# Qwiic_Quad_Relay.net
KiCad netlist of a schematic drawn in EAGLE
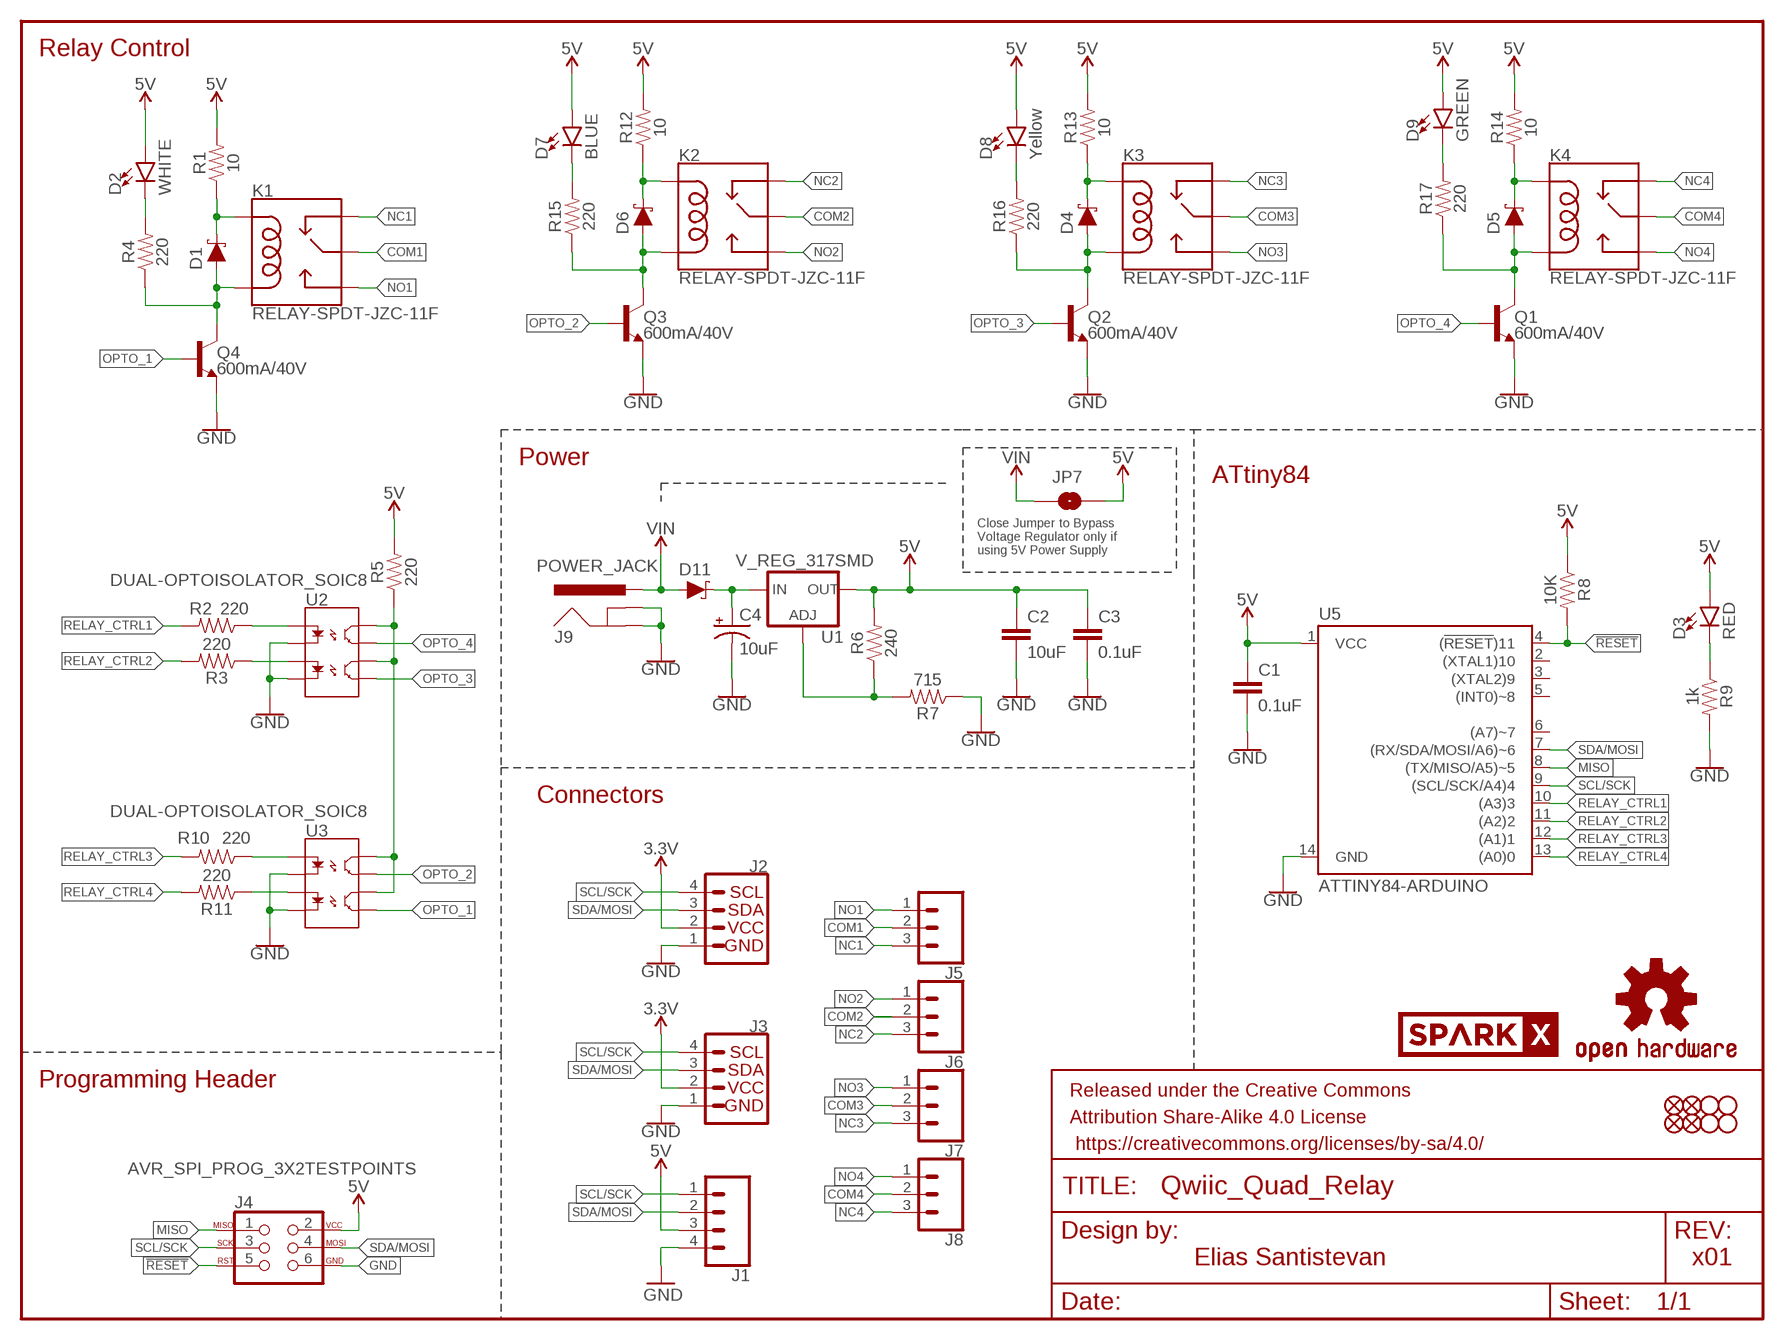
[diagram p0: schematic, sheet 1]

(export (version "E")
  (design (tool "Eeschema 10.0.6"))
  (components
    (comp (ref "C1")
      (value "0.1uF")
      (footprint "eagle-import:0603")
      (libsource (lib "eagle-import") (part "0.1UF-0603-25V-(+80/-20%)"))
    )
    (comp (ref "C2")
      (value "10uF")
      (footprint "eagle-import:0603")
      (libsource (lib "eagle-import") (part "10UF-0603-6.3V-20%"))
    )
    (comp (ref "C3")
      (value "0.1uF")
      (footprint "eagle-import:0603")
      (libsource (lib "eagle-import") (part "0.1UF-0603-25V-(+80/-20%)"))
    )
    (comp (ref "C4")
      (value "10uF")
      (footprint "eagle-import:EIA3528")
      (libsource (lib "eagle-import") (part "10UF-POLAR-EIA3528-20V-10%(TANT)"))
    )
    (comp (ref "D1")
      (value "1A/23V/620mV")
      (footprint "eagle-import:SOD-323")
      (libsource (lib "eagle-import") (part "DIODE-SCHOTTKY-BAT20J"))
    )
    (comp (ref "D2")
      (value "WHITE")
      (footprint "eagle-import:LED-0603")
      (libsource (lib "eagle-import") (part "LED-WHITE0603"))
    )
    (comp (ref "D3")
      (value "RED")
      (footprint "eagle-import:LED-0603")
      (libsource (lib "eagle-import") (part "LED-RED0603"))
    )
    (comp (ref "D4")
      (value "1A/23V/620mV")
      (footprint "eagle-import:SOD-323")
      (libsource (lib "eagle-import") (part "DIODE-SCHOTTKY-BAT20J"))
    )
    (comp (ref "D5")
      (value "1A/23V/620mV")
      (footprint "eagle-import:SOD-323")
      (libsource (lib "eagle-import") (part "DIODE-SCHOTTKY-BAT20J"))
    )
    (comp (ref "D6")
      (value "1A/23V/620mV")
      (footprint "eagle-import:SOD-323")
      (libsource (lib "eagle-import") (part "DIODE-SCHOTTKY-BAT20J"))
    )
    (comp (ref "D7")
      (value "BLUE")
      (footprint "eagle-import:LED-0603")
      (libsource (lib "eagle-import") (part "LED-BLUE0603"))
    )
    (comp (ref "D8")
      (value "Yellow")
      (footprint "eagle-import:LED-0603")
      (libsource (lib "eagle-import") (part "LED-YELLOW0603"))
    )
    (comp (ref "D9")
      (value "GREEN")
      (footprint "eagle-import:LED-0603")
      (libsource (lib "eagle-import") (part "LED-GREEN0603"))
    )
    (comp (ref "D11")
      (value "1A/40V/500mV")
      (footprint "eagle-import:SMA-DIODE")
      (libsource (lib "eagle-import") (part "DIODE-SCHOTTKY-SS14"))
    )
    (comp (ref "FRAME1")
      (value "FRAME-LETTER")
      (footprint "eagle-import:CREATIVE_COMMONS")
      (libsource (lib "eagle-import") (part "FRAME-LETTER"))
    )
    (comp (ref "J1")
      (value "CONN_041X04_NO_SILK")
      (footprint "eagle-import:1X04_NO_SILK")
      (libsource (lib "eagle-import") (part "CONN_041X04_NO_SILK"))
    )
    (comp (ref "J2")
      (value "Qwiic Right Angle")
      (footprint "eagle-import:1X04_1MM_RA")
      (libsource (lib "eagle-import") (part "I2C_STANDARDQWIIC"))
    )
    (comp (ref "J3")
      (value "Qwiic Right Angle")
      (footprint "eagle-import:1X04_1MM_RA")
      (libsource (lib "eagle-import") (part "I2C_STANDARDQWIIC"))
    )
    (comp (ref "J4")
      (value "AVR_SPI_PROG_3X2TESTPOINTS")
      (footprint "eagle-import:2X3_TEST_POINTS")
      (libsource (lib "eagle-import") (part "AVR_SPI_PROG_3X2TESTPOINTS"))
    )
    (comp (ref "J5")
      (value "CONN_03-SCREW-5MM")
      (footprint "eagle-import:SCREWTERMINAL-5MM-3")
      (libsource (lib "eagle-import") (part "CONN_03-SCREW-5MM"))
    )
    (comp (ref "J6")
      (value "CONN_03-SCREW-5MM")
      (footprint "eagle-import:SCREWTERMINAL-5MM-3")
      (libsource (lib "eagle-import") (part "CONN_03-SCREW-5MM"))
    )
    (comp (ref "J7")
      (value "CONN_03-SCREW-5MM")
      (footprint "eagle-import:SCREWTERMINAL-5MM-3")
      (libsource (lib "eagle-import") (part "CONN_03-SCREW-5MM"))
    )
    (comp (ref "J8")
      (value "CONN_03-SCREW-5MM")
      (footprint "eagle-import:SCREWTERMINAL-5MM-3")
      (libsource (lib "eagle-import") (part "CONN_03-SCREW-5MM"))
    )
    (comp (ref "J9")
      (value "POWER_JACK")
      (footprint "eagle-import:POWER_JACK_PTH")
      (libsource (lib "eagle-import") (part "POWER_JACK"))
    )
    (comp (ref "JP1")
      (value "STAND-OFF")
      (footprint "eagle-import:STAND-OFF")
      (libsource (lib "eagle-import") (part "STAND-OFF"))
    )
    (comp (ref "JP2")
      (value "FIDUCIAL1X2")
      (footprint "eagle-import:FIDUCIAL-1X2")
      (libsource (lib "eagle-import") (part "FIDUCIAL1X2"))
    )
    (comp (ref "JP3")
      (value "STAND-OFF")
      (footprint "eagle-import:STAND-OFF")
      (libsource (lib "eagle-import") (part "STAND-OFF"))
    )
    (comp (ref "JP4")
      (value "STAND-OFF")
      (footprint "eagle-import:STAND-OFF")
      (libsource (lib "eagle-import") (part "STAND-OFF"))
    )
    (comp (ref "JP5")
      (value "STAND-OFF")
      (footprint "eagle-import:STAND-OFF")
      (libsource (lib "eagle-import") (part "STAND-OFF"))
    )
    (comp (ref "JP6")
      (value "FIDUCIAL1X2")
      (footprint "eagle-import:FIDUCIAL-1X2")
      (libsource (lib "eagle-import") (part "FIDUCIAL1X2"))
    )
    (comp (ref "JP7")
      (value "JUMPER-SMT_2_NO_SILK")
      (footprint "eagle-import:SMT-JUMPER_2_NO_SILK")
      (libsource (lib "eagle-import") (part "JUMPER-SMT_2_NO_SILK"))
    )
    (comp (ref "JP8")
      (value "FIDUCIAL1X2")
      (footprint "eagle-import:FIDUCIAL-1X2")
      (libsource (lib "eagle-import") (part "FIDUCIAL1X2"))
    )
    (comp (ref "JP9")
      (value "FIDUCIAL1X2")
      (footprint "eagle-import:FIDUCIAL-1X2")
      (libsource (lib "eagle-import") (part "FIDUCIAL1X2"))
    )
    (comp (ref "K1")
      (value "RELAY-SPDT-JZC-11F")
      (footprint "eagle-import:RELAY-JZC")
      (libsource (lib "eagle-import") (part "RELAY-SPDT-JZC-11F"))
    )
    (comp (ref "K2")
      (value "RELAY-SPDT-JZC-11F")
      (footprint "eagle-import:RELAY-JZC")
      (libsource (lib "eagle-import") (part "RELAY-SPDT-JZC-11F"))
    )
    (comp (ref "K3")
      (value "RELAY-SPDT-JZC-11F")
      (footprint "eagle-import:RELAY-JZC")
      (libsource (lib "eagle-import") (part "RELAY-SPDT-JZC-11F"))
    )
    (comp (ref "K4")
      (value "RELAY-SPDT-JZC-11F")
      (footprint "eagle-import:RELAY-JZC")
      (libsource (lib "eagle-import") (part "RELAY-SPDT-JZC-11F"))
    )
    (comp (ref "LOGO1")
      (value "OSHW-LOGOS")
      (footprint "eagle-import:OSHW-LOGO-S")
      (libsource (lib "eagle-import") (part "OSHW-LOGOS"))
    )
    (comp (ref "Q1")
      (value "600mA/40V")
      (footprint "eagle-import:SOT23-3")
      (libsource (lib "eagle-import") (part "TRANS_NPN-MMBT2222AL"))
    )
    (comp (ref "Q2")
      (value "600mA/40V")
      (footprint "eagle-import:SOT23-3")
      (libsource (lib "eagle-import") (part "TRANS_NPN-MMBT2222AL"))
    )
    (comp (ref "Q3")
      (value "600mA/40V")
      (footprint "eagle-import:SOT23-3")
      (libsource (lib "eagle-import") (part "TRANS_NPN-MMBT2222AL"))
    )
    (comp (ref "Q4")
      (value "600mA/40V")
      (footprint "eagle-import:SOT23-3")
      (libsource (lib "eagle-import") (part "TRANS_NPN-MMBT2222AL"))
    )
    (comp (ref "R1")
      (value "10")
      (footprint "eagle-import:0603")
      (libsource (lib "eagle-import") (part "47KOHM-0603-1/10W-1%"))
    )
    (comp (ref "R2")
      (value "220")
      (footprint "eagle-import:0603")
      (libsource (lib "eagle-import") (part "220OHM-0603-1/10W-1%"))
    )
    (comp (ref "R3")
      (value "220")
      (footprint "eagle-import:0603")
      (libsource (lib "eagle-import") (part "220OHM-0603-1/10W-1%"))
    )
    (comp (ref "R4")
      (value "220")
      (footprint "eagle-import:0603")
      (libsource (lib "eagle-import") (part "220OHM-0603-1/10W-1%"))
    )
    (comp (ref "R5")
      (value "220")
      (footprint "eagle-import:0603")
      (libsource (lib "eagle-import") (part "220OHM-0603-1/10W-1%"))
    )
    (comp (ref "R6")
      (value "240")
      (footprint "eagle-import:0603")
      (libsource (lib "eagle-import") (part "240OHM-0603-1/10W-1%"))
    )
    (comp (ref "R7")
      (value "715")
      (footprint "eagle-import:0603")
      (libsource (lib "eagle-import") (part "715OHM-0603-1/10W-1%"))
    )
    (comp (ref "R8")
      (value "10K")
      (footprint "eagle-import:0603")
      (libsource (lib "eagle-import") (part "330OHM-0603-1/10W-1%"))
    )
    (comp (ref "R9")
      (value "1k")
      (footprint "eagle-import:0603")
      (libsource (lib "eagle-import") (part "330OHM-0603-1/10W-1%"))
    )
    (comp (ref "R10")
      (value "220")
      (footprint "eagle-import:0603")
      (libsource (lib "eagle-import") (part "220OHM-0603-1/10W-1%"))
    )
    (comp (ref "R11")
      (value "220")
      (footprint "eagle-import:0603")
      (libsource (lib "eagle-import") (part "220OHM-0603-1/10W-1%"))
    )
    (comp (ref "R12")
      (value "10")
      (footprint "eagle-import:0603")
      (libsource (lib "eagle-import") (part "47KOHM-0603-1/10W-1%"))
    )
    (comp (ref "R13")
      (value "10")
      (footprint "eagle-import:0603")
      (libsource (lib "eagle-import") (part "47KOHM-0603-1/10W-1%"))
    )
    (comp (ref "R14")
      (value "10")
      (footprint "eagle-import:0603")
      (libsource (lib "eagle-import") (part "47KOHM-0603-1/10W-1%"))
    )
    (comp (ref "R15")
      (value "220")
      (footprint "eagle-import:0603")
      (libsource (lib "eagle-import") (part "220OHM-0603-1/10W-1%"))
    )
    (comp (ref "R16")
      (value "220")
      (footprint "eagle-import:0603")
      (libsource (lib "eagle-import") (part "220OHM-0603-1/10W-1%"))
    )
    (comp (ref "R17")
      (value "220")
      (footprint "eagle-import:0603")
      (libsource (lib "eagle-import") (part "220OHM-0603-1/10W-1%"))
    )
    (comp (ref "U$12")
      (value "SPARKX-LOGO4")
      (footprint "eagle-import:SPARKX-MEDIUM")
      (libsource (lib "eagle-import") (part "SPARKX-LOGO4"))
    )
    (comp (ref "U1")
      (value "V_REG_317SMD")
      (footprint "eagle-import:SOT223")
      (libsource (lib "eagle-import") (part "V_REG_317SMD"))
    )
    (comp (ref "U2")
      (value "DUAL-OPTOISOLATOR_SOIC8")
      (footprint "eagle-import:SO08")
      (libsource (lib "eagle-import") (part "DUAL-OPTOISOLATOR_SOIC8"))
    )
    (comp (ref "U3")
      (value "DUAL-OPTOISOLATOR_SOIC8")
      (footprint "eagle-import:SO08")
      (libsource (lib "eagle-import") (part "DUAL-OPTOISOLATOR_SOIC8"))
    )
    (comp (ref "U5")
      (value "ATTINY84-ARDUINO")
      (footprint "eagle-import:SO14")
      (libsource (lib "eagle-import") (part "ATTINY84-ARDUINO"))
    )
  )
  (nets
    (net (code "1") (name "/~{RESET}") (class "Default")
      (node (ref "J4") (pin "5") (pinfunction "5_5") (pintype "passive"))
      (node (ref "R8") (pin "2") (pinfunction "2_2") (pintype "passive"))
      (node (ref "U5") (pin "4") (pinfunction "(~{RESET})11_4") (pintype "bidirectional"))
    )
    (net (code "2") (name "3.3V") (class "Default")
      (node (ref "J2") (pin "2") (pinfunction "2_2") (pintype "power_in"))
      (node (ref "J3") (pin "2") (pinfunction "2_2") (pintype "power_in"))
    )
    (net (code "3") (name "5V") (class "Default")
      (node (ref "C1") (pin "1") (pinfunction "1_1") (pintype "passive"))
      (node (ref "C2") (pin "1") (pinfunction "1_1") (pintype "passive"))
      (node (ref "C3") (pin "1") (pinfunction "1_1") (pintype "passive"))
      (node (ref "D2") (pin "A") (pinfunction "A_A") (pintype "passive"))
      (node (ref "D3") (pin "A") (pinfunction "A_A") (pintype "passive"))
      (node (ref "D7") (pin "A") (pinfunction "A_A") (pintype "passive"))
      (node (ref "D8") (pin "A") (pinfunction "A_A") (pintype "passive"))
      (node (ref "D9") (pin "A") (pinfunction "A_A") (pintype "passive"))
      (node (ref "J1") (pin "3") (pinfunction "3_3") (pintype "passive"))
      (node (ref "J4") (pin "2") (pinfunction "2_2") (pintype "passive"))
      (node (ref "JP7") (pin "2") (pinfunction "2_2") (pintype "passive"))
      (node (ref "R1") (pin "2") (pinfunction "2_2") (pintype "passive"))
      (node (ref "R12") (pin "2") (pinfunction "2_2") (pintype "passive"))
      (node (ref "R13") (pin "2") (pinfunction "2_2") (pintype "passive"))
      (node (ref "R14") (pin "2") (pinfunction "2_2") (pintype "passive"))
      (node (ref "R5") (pin "2") (pinfunction "2_2") (pintype "passive"))
      (node (ref "R6") (pin "2") (pinfunction "2_2") (pintype "passive"))
      (node (ref "R8") (pin "1") (pinfunction "1_1") (pintype "passive"))
      (node (ref "U1") (pin "2") (pinfunction "OUT_2") (pintype "output"))
      (node (ref "U5") (pin "1") (pinfunction "VCC_1") (pintype "bidirectional"))
    )
    (net (code "4") (name "COM1") (class "Default")
      (node (ref "J5") (pin "2") (pinfunction "2_2") (pintype "passive"))
      (node (ref "K1") (pin "4") (pinfunction "MAIN_4") (pintype "bidirectional"))
    )
    (net (code "5") (name "COM2") (class "Default")
      (node (ref "J6") (pin "2") (pinfunction "2_2") (pintype "passive"))
      (node (ref "K2") (pin "4") (pinfunction "MAIN_4") (pintype "bidirectional"))
    )
    (net (code "6") (name "COM3") (class "Default")
      (node (ref "J7") (pin "2") (pinfunction "2_2") (pintype "passive"))
      (node (ref "K3") (pin "4") (pinfunction "MAIN_4") (pintype "bidirectional"))
    )
    (net (code "7") (name "COM4") (class "Default")
      (node (ref "J8") (pin "2") (pinfunction "2_2") (pintype "passive"))
      (node (ref "K4") (pin "4") (pinfunction "MAIN_4") (pintype "bidirectional"))
    )
    (net (code "8") (name "GND") (class "Default")
      (node (ref "C1") (pin "2") (pinfunction "2_2") (pintype "passive"))
      (node (ref "C2") (pin "2") (pinfunction "2_2") (pintype "passive"))
      (node (ref "C3") (pin "2") (pinfunction "2_2") (pintype "passive"))
      (node (ref "C4") (pin "C") (pinfunction "-_C") (pintype "passive"))
      (node (ref "J1") (pin "4") (pinfunction "4_4") (pintype "passive"))
      (node (ref "J2") (pin "1") (pinfunction "1_1") (pintype "power_in"))
      (node (ref "J3") (pin "1") (pinfunction "1_1") (pintype "power_in"))
      (node (ref "J4") (pin "6") (pinfunction "6_6") (pintype "passive"))
      (node (ref "J9") (pin "GND") (pinfunction "GND_GND") (pintype "bidirectional"))
      (node (ref "J9") (pin "GNDBREAK") (pinfunction "GNDBREAK_GNDBREAK") (pintype "bidirectional"))
      (node (ref "Q1") (pin "2") (pinfunction "E_2") (pintype "passive"))
      (node (ref "Q2") (pin "2") (pinfunction "E_2") (pintype "passive"))
      (node (ref "Q3") (pin "2") (pinfunction "E_2") (pintype "passive"))
      (node (ref "Q4") (pin "2") (pinfunction "E_2") (pintype "passive"))
      (node (ref "R7") (pin "1") (pinfunction "1_1") (pintype "passive"))
      (node (ref "R9") (pin "2") (pinfunction "2_2") (pintype "passive"))
      (node (ref "U2") (pin "2") (pinfunction "C1_2") (pintype "bidirectional"))
      (node (ref "U2") (pin "4") (pinfunction "C2_4") (pintype "bidirectional"))
      (node (ref "U3") (pin "2") (pinfunction "C1_2") (pintype "bidirectional"))
      (node (ref "U3") (pin "4") (pinfunction "C2_4") (pintype "bidirectional"))
      (node (ref "U5") (pin "14") (pinfunction "GND_14") (pintype "bidirectional"))
    )
    (net (code "9") (name "MISO") (class "Default")
      (node (ref "J4") (pin "1") (pinfunction "1_1") (pintype "passive"))
      (node (ref "U5") (pin "8") (pinfunction "(TX/MISO/A5)~{5}_8") (pintype "bidirectional"))
    )
    (net (code "10") (name "NC1") (class "Default")
      (node (ref "J5") (pin "3") (pinfunction "3_3") (pintype "passive"))
      (node (ref "K1") (pin "2") (pinfunction "NC_2") (pintype "bidirectional"))
    )
    (net (code "11") (name "NC2") (class "Default")
      (node (ref "J6") (pin "3") (pinfunction "3_3") (pintype "passive"))
      (node (ref "K2") (pin "2") (pinfunction "NC_2") (pintype "bidirectional"))
    )
    (net (code "12") (name "NC3") (class "Default")
      (node (ref "J7") (pin "3") (pinfunction "3_3") (pintype "passive"))
      (node (ref "K3") (pin "2") (pinfunction "NC_2") (pintype "bidirectional"))
    )
    (net (code "13") (name "NC4") (class "Default")
      (node (ref "J8") (pin "3") (pinfunction "3_3") (pintype "passive"))
      (node (ref "K4") (pin "2") (pinfunction "NC_2") (pintype "bidirectional"))
    )
    (net (code "14") (name "NO1") (class "Default")
      (node (ref "J5") (pin "1") (pinfunction "1_1") (pintype "passive"))
      (node (ref "K1") (pin "3") (pinfunction "NO_3") (pintype "bidirectional"))
    )
    (net (code "15") (name "NO2") (class "Default")
      (node (ref "J6") (pin "1") (pinfunction "1_1") (pintype "passive"))
      (node (ref "K2") (pin "3") (pinfunction "NO_3") (pintype "bidirectional"))
    )
    (net (code "16") (name "NO3") (class "Default")
      (node (ref "J7") (pin "1") (pinfunction "1_1") (pintype "passive"))
      (node (ref "K3") (pin "3") (pinfunction "NO_3") (pintype "bidirectional"))
    )
    (net (code "17") (name "NO4") (class "Default")
      (node (ref "J8") (pin "1") (pinfunction "1_1") (pintype "passive"))
      (node (ref "K4") (pin "3") (pinfunction "NO_3") (pintype "bidirectional"))
    )
    (net (code "18") (name "Net-(C4-+)") (class "Default")
      (node (ref "C4") (pin "A") (pinfunction "+_A") (pintype "passive"))
      (node (ref "D11") (pin "C") (pinfunction "C_C") (pintype "passive"))
      (node (ref "U1") (pin "3") (pinfunction "IN_3") (pintype "input"))
    )
    (net (code "19") (name "Net-(D2-PadC)") (class "Default")
      (node (ref "D2") (pin "C") (pinfunction "C_C") (pintype "passive"))
      (node (ref "R4") (pin "2") (pinfunction "2_2") (pintype "passive"))
    )
    (net (code "20") (name "Net-(D3-PadC)") (class "Default")
      (node (ref "D3") (pin "C") (pinfunction "C_C") (pintype "passive"))
      (node (ref "R9") (pin "1") (pinfunction "1_1") (pintype "passive"))
    )
    (net (code "21") (name "Net-(D7-PadC)") (class "Default")
      (node (ref "D7") (pin "C") (pinfunction "C_C") (pintype "passive"))
      (node (ref "R15") (pin "2") (pinfunction "2_2") (pintype "passive"))
    )
    (net (code "22") (name "Net-(D8-PadC)") (class "Default")
      (node (ref "D8") (pin "C") (pinfunction "C_C") (pintype "passive"))
      (node (ref "R16") (pin "2") (pinfunction "2_2") (pintype "passive"))
    )
    (net (code "23") (name "Net-(D9-PadC)") (class "Default")
      (node (ref "D9") (pin "C") (pinfunction "C_C") (pintype "passive"))
      (node (ref "R17") (pin "2") (pinfunction "2_2") (pintype "passive"))
    )
    (net (code "24") (name "Net-(K1-COIL1)") (class "Default")
      (node (ref "D1") (pin "C") (pinfunction "C_C") (pintype "passive"))
      (node (ref "K1") (pin "5") (pinfunction "COIL1_5") (pintype "bidirectional"))
      (node (ref "R1") (pin "1") (pinfunction "1_1") (pintype "passive"))
    )
    (net (code "25") (name "Net-(K1-COIL2)") (class "Default")
      (node (ref "D1") (pin "A") (pinfunction "A_A") (pintype "passive"))
      (node (ref "K1") (pin "1") (pinfunction "COIL2_1") (pintype "bidirectional"))
      (node (ref "Q4") (pin "3") (pinfunction "C_3") (pintype "passive"))
      (node (ref "R4") (pin "1") (pinfunction "1_1") (pintype "passive"))
    )
    (net (code "26") (name "Net-(K2-COIL1)") (class "Default")
      (node (ref "D6") (pin "C") (pinfunction "C_C") (pintype "passive"))
      (node (ref "K2") (pin "5") (pinfunction "COIL1_5") (pintype "bidirectional"))
      (node (ref "R12") (pin "1") (pinfunction "1_1") (pintype "passive"))
    )
    (net (code "27") (name "Net-(K2-COIL2)") (class "Default")
      (node (ref "D6") (pin "A") (pinfunction "A_A") (pintype "passive"))
      (node (ref "K2") (pin "1") (pinfunction "COIL2_1") (pintype "bidirectional"))
      (node (ref "Q3") (pin "3") (pinfunction "C_3") (pintype "passive"))
      (node (ref "R15") (pin "1") (pinfunction "1_1") (pintype "passive"))
    )
    (net (code "28") (name "Net-(K3-COIL1)") (class "Default")
      (node (ref "D4") (pin "C") (pinfunction "C_C") (pintype "passive"))
      (node (ref "K3") (pin "5") (pinfunction "COIL1_5") (pintype "bidirectional"))
      (node (ref "R13") (pin "1") (pinfunction "1_1") (pintype "passive"))
    )
    (net (code "29") (name "Net-(K3-COIL2)") (class "Default")
      (node (ref "D4") (pin "A") (pinfunction "A_A") (pintype "passive"))
      (node (ref "K3") (pin "1") (pinfunction "COIL2_1") (pintype "bidirectional"))
      (node (ref "Q2") (pin "3") (pinfunction "C_3") (pintype "passive"))
      (node (ref "R16") (pin "1") (pinfunction "1_1") (pintype "passive"))
    )
    (net (code "30") (name "Net-(K4-COIL1)") (class "Default")
      (node (ref "D5") (pin "C") (pinfunction "C_C") (pintype "passive"))
      (node (ref "K4") (pin "5") (pinfunction "COIL1_5") (pintype "bidirectional"))
      (node (ref "R14") (pin "1") (pinfunction "1_1") (pintype "passive"))
    )
    (net (code "31") (name "Net-(K4-COIL2)") (class "Default")
      (node (ref "D5") (pin "A") (pinfunction "A_A") (pintype "passive"))
      (node (ref "K4") (pin "1") (pinfunction "COIL2_1") (pintype "bidirectional"))
      (node (ref "Q1") (pin "3") (pinfunction "C_3") (pintype "passive"))
      (node (ref "R17") (pin "1") (pinfunction "1_1") (pintype "passive"))
    )
    (net (code "32") (name "Net-(U1-ADJ)") (class "Default")
      (node (ref "R6") (pin "1") (pinfunction "1_1") (pintype "passive"))
      (node (ref "R7") (pin "2") (pinfunction "2_2") (pintype "passive"))
      (node (ref "U1") (pin "1") (pinfunction "ADJ_1") (pintype "input"))
    )
    (net (code "33") (name "Net-(U2-A1)") (class "Default")
      (node (ref "R2") (pin "1") (pinfunction "1_1") (pintype "passive"))
      (node (ref "U2") (pin "1") (pinfunction "A1_1") (pintype "bidirectional"))
    )
    (net (code "34") (name "Net-(U2-A2)") (class "Default")
      (node (ref "R3") (pin "1") (pinfunction "1_1") (pintype "passive"))
      (node (ref "U2") (pin "3") (pinfunction "A2_3") (pintype "bidirectional"))
    )
    (net (code "35") (name "Net-(U2-CL1)") (class "Default")
      (node (ref "R5") (pin "1") (pinfunction "1_1") (pintype "passive"))
      (node (ref "U2") (pin "6") (pinfunction "CL2_6") (pintype "bidirectional"))
      (node (ref "U2") (pin "8") (pinfunction "CL1_8") (pintype "bidirectional"))
      (node (ref "U3") (pin "6") (pinfunction "CL2_6") (pintype "bidirectional"))
      (node (ref "U3") (pin "8") (pinfunction "CL1_8") (pintype "bidirectional"))
    )
    (net (code "36") (name "Net-(U3-A1)") (class "Default")
      (node (ref "R10") (pin "1") (pinfunction "1_1") (pintype "passive"))
      (node (ref "U3") (pin "1") (pinfunction "A1_1") (pintype "bidirectional"))
    )
    (net (code "37") (name "Net-(U3-A2)") (class "Default")
      (node (ref "R11") (pin "1") (pinfunction "1_1") (pintype "passive"))
      (node (ref "U3") (pin "3") (pinfunction "A2_3") (pintype "bidirectional"))
    )
    (net (code "38") (name "OPTO_1") (class "Default")
      (node (ref "Q4") (pin "1") (pinfunction "B_1") (pintype "passive"))
      (node (ref "U3") (pin "5") (pinfunction "EM2_5") (pintype "bidirectional"))
    )
    (net (code "39") (name "OPTO_2") (class "Default")
      (node (ref "Q3") (pin "1") (pinfunction "B_1") (pintype "passive"))
      (node (ref "U3") (pin "7") (pinfunction "EM1_7") (pintype "bidirectional"))
    )
    (net (code "40") (name "OPTO_3") (class "Default")
      (node (ref "Q2") (pin "1") (pinfunction "B_1") (pintype "passive"))
      (node (ref "U2") (pin "5") (pinfunction "EM2_5") (pintype "bidirectional"))
    )
    (net (code "41") (name "OPTO_4") (class "Default")
      (node (ref "Q1") (pin "1") (pinfunction "B_1") (pintype "passive"))
      (node (ref "U2") (pin "7") (pinfunction "EM1_7") (pintype "bidirectional"))
    )
    (net (code "42") (name "RELAY_CTRL1") (class "Default")
      (node (ref "R2") (pin "2") (pinfunction "2_2") (pintype "passive"))
      (node (ref "U5") (pin "10") (pinfunction "(A3)3_10") (pintype "bidirectional"))
    )
    (net (code "43") (name "RELAY_CTRL2") (class "Default")
      (node (ref "R3") (pin "2") (pinfunction "2_2") (pintype "passive"))
      (node (ref "U5") (pin "11") (pinfunction "(A2)2_11") (pintype "bidirectional"))
    )
    (net (code "44") (name "RELAY_CTRL3") (class "Default")
      (node (ref "R10") (pin "2") (pinfunction "2_2") (pintype "passive"))
      (node (ref "U5") (pin "12") (pinfunction "(A1)1_12") (pintype "bidirectional"))
    )
    (net (code "45") (name "RELAY_CTRL4") (class "Default")
      (node (ref "R11") (pin "2") (pinfunction "2_2") (pintype "passive"))
      (node (ref "U5") (pin "13") (pinfunction "(A0)0_13") (pintype "bidirectional"))
    )
    (net (code "46") (name "SCL{slash}SCK") (class "Default")
      (node (ref "J1") (pin "1") (pinfunction "1_1") (pintype "passive"))
      (node (ref "J2") (pin "4") (pinfunction "4_4") (pintype "passive"))
      (node (ref "J3") (pin "4") (pinfunction "4_4") (pintype "passive"))
      (node (ref "J4") (pin "3") (pinfunction "3_3") (pintype "passive"))
      (node (ref "U5") (pin "9") (pinfunction "(SCL/SCK/A4)4_9") (pintype "bidirectional"))
    )
    (net (code "47") (name "SDA{slash}MOSI") (class "Default")
      (node (ref "J1") (pin "2") (pinfunction "2_2") (pintype "passive"))
      (node (ref "J2") (pin "3") (pinfunction "3_3") (pintype "passive"))
      (node (ref "J3") (pin "3") (pinfunction "3_3") (pintype "passive"))
      (node (ref "J4") (pin "4") (pinfunction "4_4") (pintype "passive"))
      (node (ref "U5") (pin "7") (pinfunction "(RX/SDA/MOSI/A6)~{6}_7") (pintype "bidirectional"))
    )
    (net (code "48") (name "VIN") (class "Default")
      (node (ref "D11") (pin "A") (pinfunction "A_A") (pintype "passive"))
      (node (ref "J9") (pin "PWR") (pinfunction "PWR_PWR") (pintype "bidirectional"))
      (node (ref "JP7") (pin "1") (pinfunction "1_1") (pintype "passive"))
    )
    (net (code "49") (name "unconnected-(U5-(A7)~{7}-Pad6)") (class "Default")
      (node (ref "U5") (pin "6") (pinfunction "(A7)~{7}_6") (pintype "bidirectional"))
    )
    (net (code "50") (name "unconnected-(U5-(INT0)~{8}-Pad5)") (class "Default")
      (node (ref "U5") (pin "5") (pinfunction "(INT0)~{8}_5") (pintype "bidirectional"))
    )
    (net (code "51") (name "unconnected-(U5-(XTAL1)10-Pad2)") (class "Default")
      (node (ref "U5") (pin "2") (pinfunction "(XTAL1)10_2") (pintype "bidirectional"))
    )
    (net (code "52") (name "unconnected-(U5-(XTAL2)9-Pad3)") (class "Default")
      (node (ref "U5") (pin "3") (pinfunction "(XTAL2)9_3") (pintype "bidirectional"))
    )
  )
)
